# NuTube_Screamer_v1_1.net
KiCad netlist of a schematic drawn in EAGLE
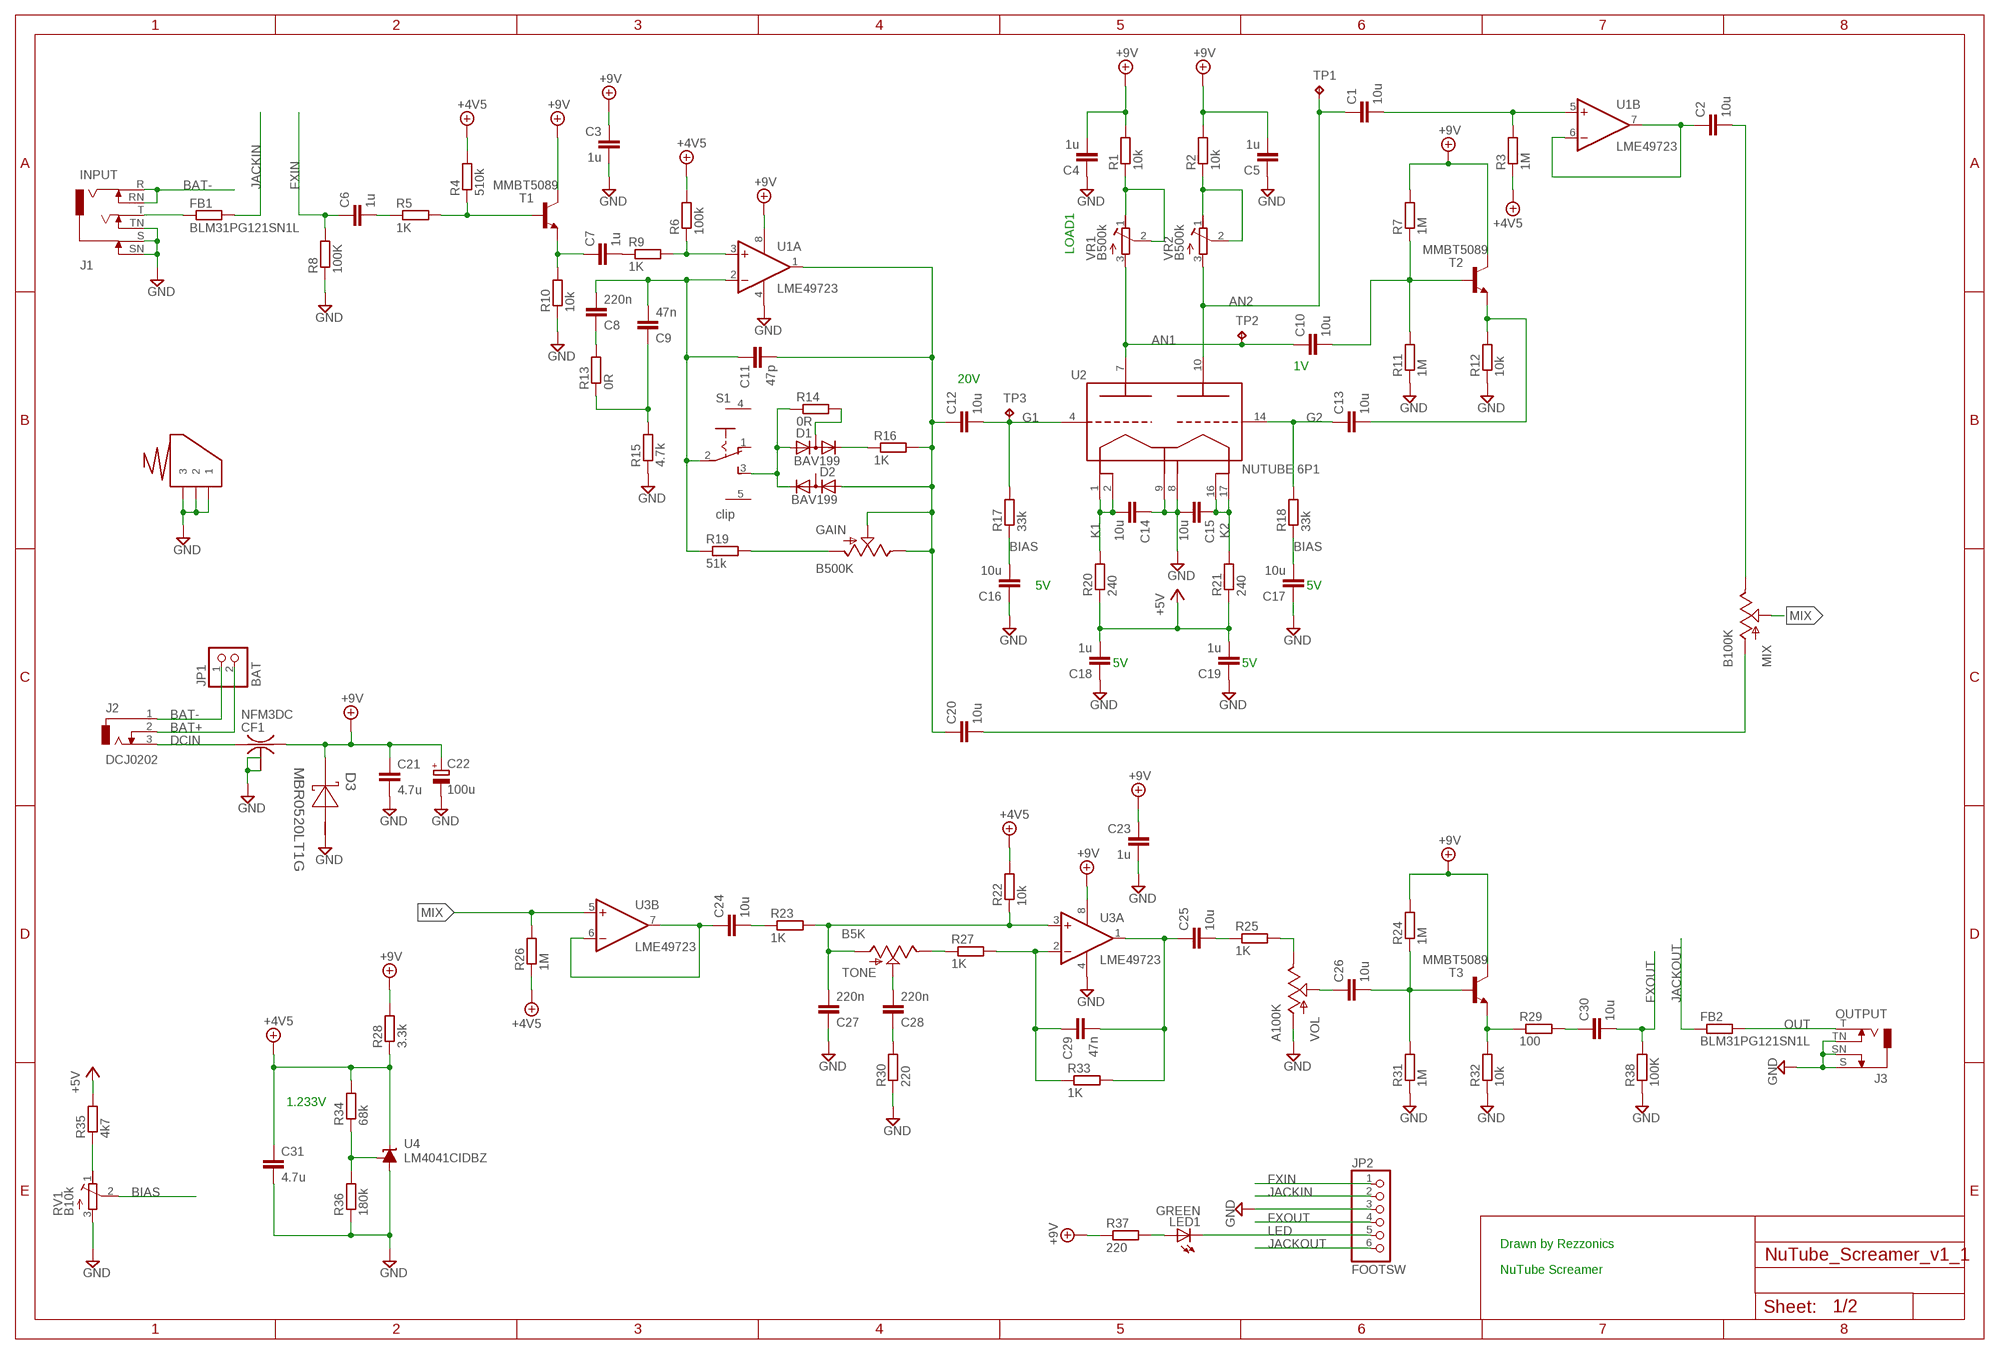
[diagram p0: schematic, sheet 1]
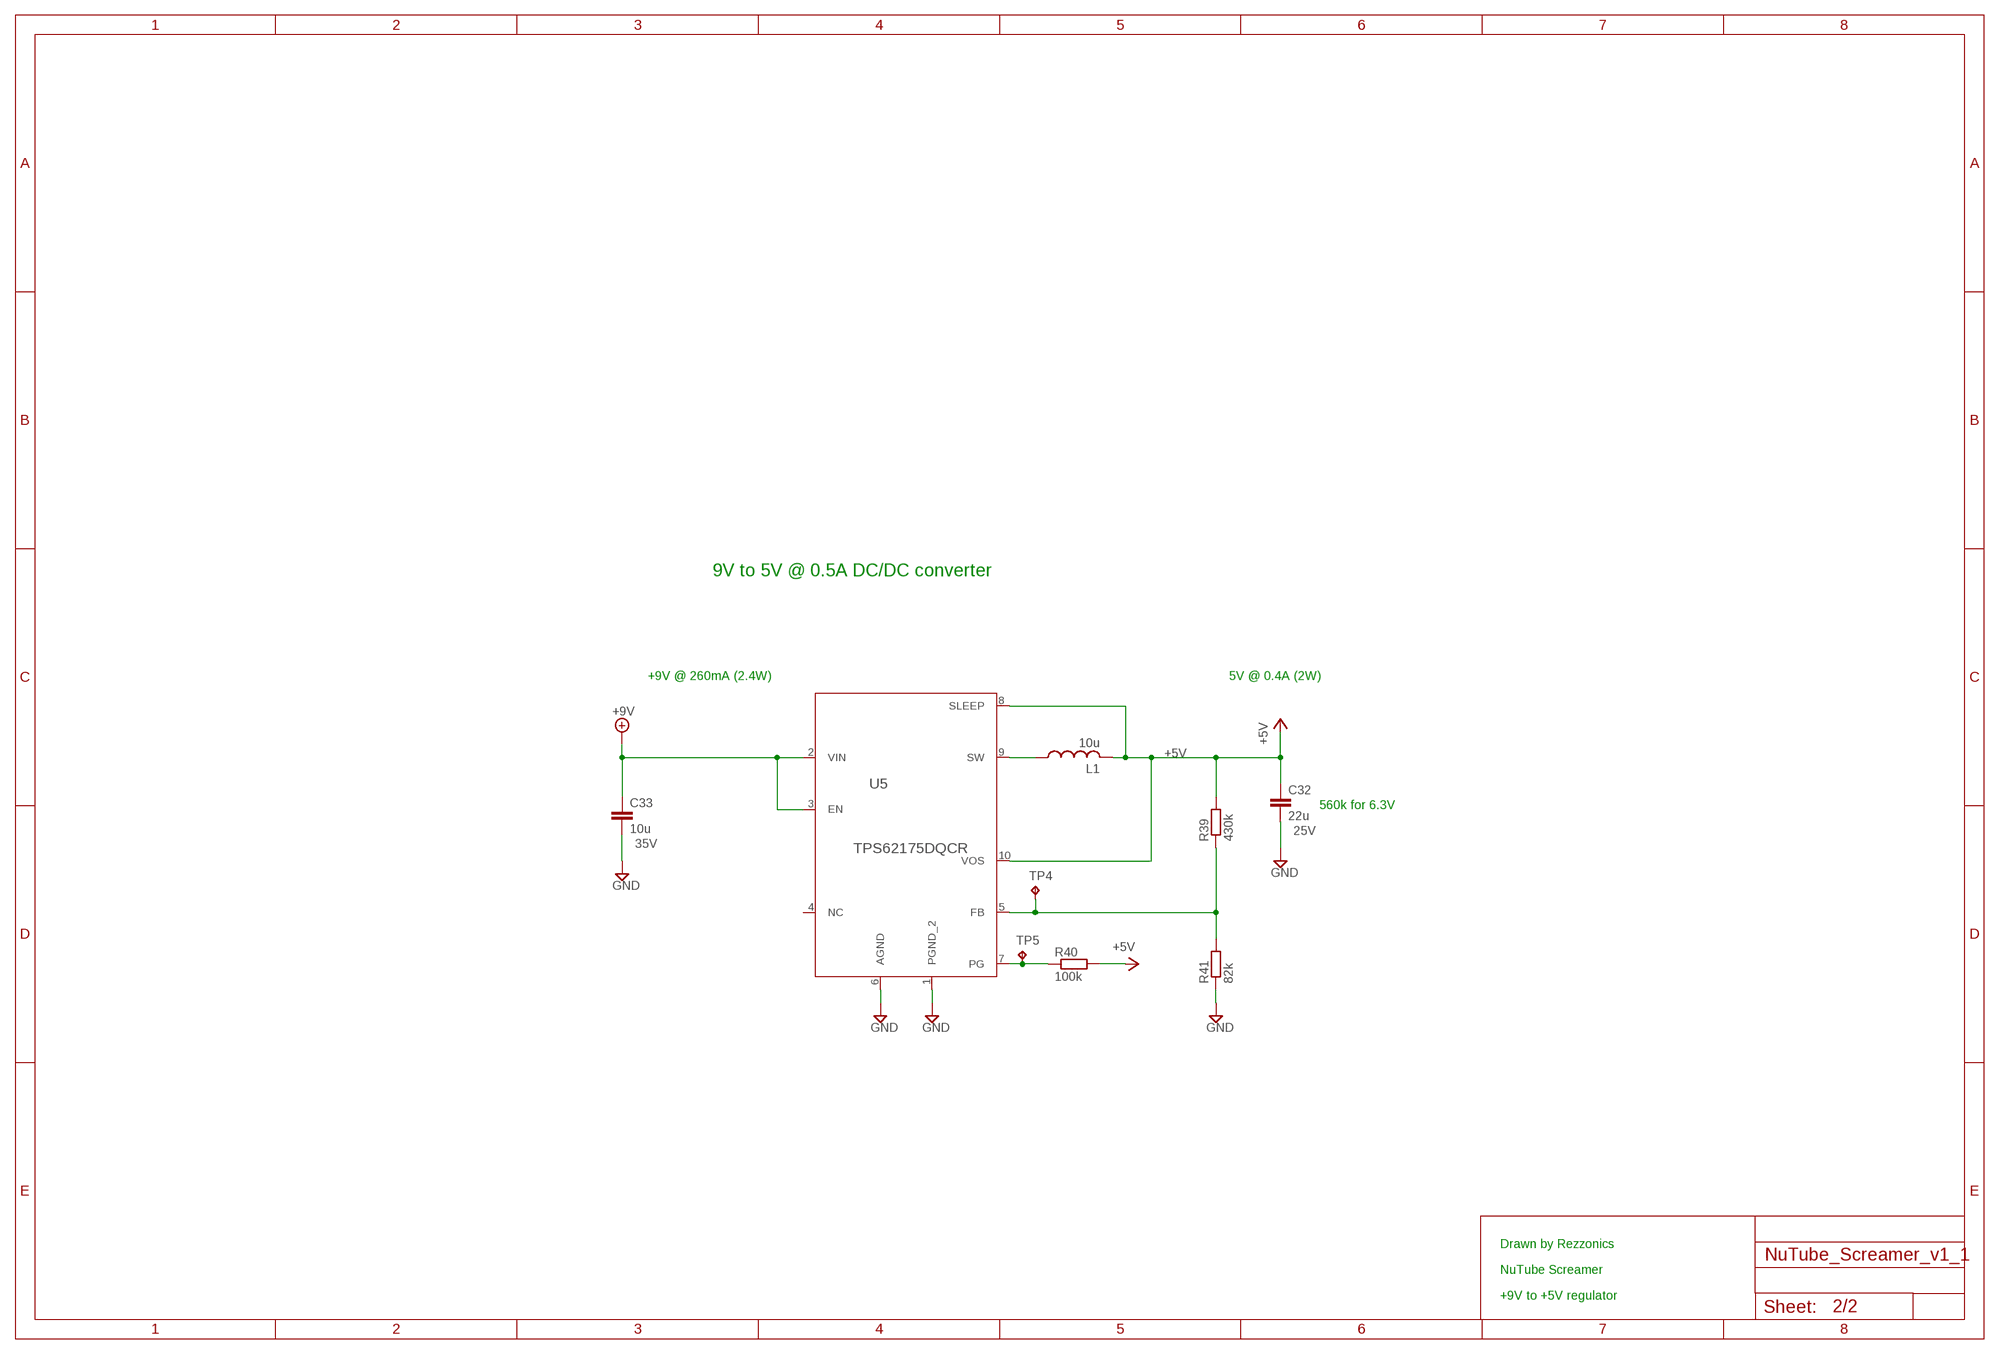
[diagram p1: schematic, sheet 2]

(export (version "E")
  (design (tool "Eeschema 10.0.6"))
  (components
    (comp (ref "C1")
      (value "10u")
      (footprint "eagle-import:C0805K")
      (fields (field (name "MPN") "GRM21BR6YA106KE43L"))
      (libsource (lib "eagle-import") (part "C-EUC0805K"))
    )
    (comp (ref "C2")
      (value "10u")
      (footprint "eagle-import:C0805K")
      (fields (field (name "MPN") "GRM21BR6YA106KE43L"))
      (libsource (lib "eagle-import") (part "C-EUC0805K"))
    )
    (comp (ref "C3")
      (value "1u")
      (footprint "eagle-import:C0603K")
      (fields (field (name "MPN") "GRM188R71H104KA93D") (field (name "PARTNO") "C1608X7R1V105K080AE"))
      (libsource (lib "eagle-import") (part "C-EUC0603K"))
    )
    (comp (ref "C4")
      (value "1u")
      (footprint "eagle-import:C0603K")
      (fields (field (name "MPN") "C1608X5R1H105K080AB") (field (name "PARTNO") "C1608X7R1V105K080AE"))
      (libsource (lib "eagle-import") (part "C-EUC0603K"))
    )
    (comp (ref "C5")
      (value "1u")
      (footprint "eagle-import:C0603K")
      (fields (field (name "MPN") "C1608X5R1H105K080AB") (field (name "PARTNO") "C1608X7R1V105K080AE"))
      (libsource (lib "eagle-import") (part "C-EUC0603K"))
    )
    (comp (ref "C6")
      (value "1u")
      (footprint "eagle-import:C0603K")
      (fields (field (name "MPN") "GRM188R71H104KA93D") (field (name "PARTNO") "C1608X7R1V105K080AE"))
      (libsource (lib "eagle-import") (part "C-EUC0603K"))
    )
    (comp (ref "C7")
      (value "1u")
      (footprint "eagle-import:C0603K")
      (fields (field (name "MPN") "GRM188R71H104KA93D") (field (name "PARTNO") "C1608X7R1V105K080AE"))
      (libsource (lib "eagle-import") (part "C-EUC0603K"))
    )
    (comp (ref "C8")
      (value "220n")
      (footprint "eagle-import:C0603K")
      (fields (field (name "MPN") "GRM188R71H104KA93D") (field (name "PARTNO") "GRM188R61H224KAC4D"))
      (libsource (lib "eagle-import") (part "C-EUC0603K"))
    )
    (comp (ref "C9")
      (value "47n")
      (footprint "eagle-import:C0603K")
      (fields (field (name "MPN") "GRM188R71H104KA93D") (field (name "PARTNO") "06035D473MAT2A"))
      (libsource (lib "eagle-import") (part "C-EUC0603K"))
    )
    (comp (ref "C10")
      (value "10u")
      (footprint "eagle-import:C0805K")
      (fields (field (name "MPN") "GRM21BR6YA106KE43L"))
      (libsource (lib "eagle-import") (part "C-EUC0805K"))
    )
    (comp (ref "C11")
      (value "47p")
      (footprint "eagle-import:C0603K")
      (fields (field (name "MPN") "GRM188R71H104KA93D") (field (name "PARTNO") "GCM1885C2A470JA16D"))
      (libsource (lib "eagle-import") (part "C-EUC0603K"))
    )
    (comp (ref "C12")
      (value "10u")
      (footprint "eagle-import:C0805K")
      (fields (field (name "MPN") "GRM21BR6YA106KE43L"))
      (libsource (lib "eagle-import") (part "C-EUC0805K"))
    )
    (comp (ref "C13")
      (value "10u")
      (footprint "eagle-import:C0805K")
      (fields (field (name "PARTNO") "GRM21BR6YA106KE43L"))
      (libsource (lib "eagle-import") (part "C-EUC0805K"))
    )
    (comp (ref "C14")
      (value "10u")
      (footprint "eagle-import:C0805K")
      (fields (field (name "MPN") "GRM21BR6YA106KE43L"))
      (libsource (lib "eagle-import") (part "C-EUC0805K"))
    )
    (comp (ref "C15")
      (value "10u")
      (footprint "eagle-import:C0805K")
      (fields (field (name "MPN") "GRM21BR6YA106KE43L"))
      (libsource (lib "eagle-import") (part "C-EUC0805K"))
    )
    (comp (ref "C16")
      (value "10u")
      (footprint "eagle-import:C0805K")
      (fields (field (name "MPN") "GRM21BR6YA106KE43L"))
      (libsource (lib "eagle-import") (part "C-EUC0805K"))
    )
    (comp (ref "C17")
      (value "10u")
      (footprint "eagle-import:C0805K")
      (fields (field (name "MPN") "GRM21BR6YA106KE43L"))
      (libsource (lib "eagle-import") (part "C-EUC0805K"))
    )
    (comp (ref "C18")
      (value "1u")
      (footprint "eagle-import:C0603K")
      (fields (field (name "MPN") "C1608X5R1H105K080AB") (field (name "PARTNO") "C1608X7R1V105K080AE"))
      (libsource (lib "eagle-import") (part "C-EUC0603K"))
    )
    (comp (ref "C19")
      (value "1u")
      (footprint "eagle-import:C0603K")
      (fields (field (name "MPN") "C1608X5R1H105K080AB") (field (name "PARTNO") "C1608X7R1V105K080AE"))
      (libsource (lib "eagle-import") (part "C-EUC0603K"))
    )
    (comp (ref "C20")
      (value "10u")
      (footprint "eagle-import:C0805K")
      (fields (field (name "MPN") "GRM21BR6YA106KE43L"))
      (libsource (lib "eagle-import") (part "C-EUC0805K"))
    )
    (comp (ref "C21")
      (value "4.7u")
      (footprint "eagle-import:C0805K")
      (fields (field (name "MPN") "GRM21BR61E475KA12L") (field (name "PARTNO") "C2012X5R1E475K125AB"))
      (libsource (lib "eagle-import") (part "C-EUC0805K"))
    )
    (comp (ref "C22")
      (value "100u")
      (footprint "eagle-import:PANASONIC_D")
      (fields (field (name "MPN") "EEE-1VA101XP"))
      (libsource (lib "eagle-import") (part "CPOL-EUD"))
    )
    (comp (ref "C23")
      (value "1u")
      (footprint "eagle-import:C0603K")
      (fields (field (name "MPN") "GRM188R71H104KA93D") (field (name "PARTNO") "C1608X7R1V105K080AE"))
      (libsource (lib "eagle-import") (part "C-EUC0603K"))
    )
    (comp (ref "C24")
      (value "10u")
      (footprint "eagle-import:C0805K")
      (fields (field (name "MPN") "GRM21BR6YA106KE43L"))
      (libsource (lib "eagle-import") (part "C-EUC0805K"))
    )
    (comp (ref "C25")
      (value "10u")
      (footprint "eagle-import:C0805K")
      (fields (field (name "MPN") "GRM21BR6YA106KE43L"))
      (libsource (lib "eagle-import") (part "C-EUC0805K"))
    )
    (comp (ref "C26")
      (value "10u")
      (footprint "eagle-import:C0805K")
      (fields (field (name "MPN") "GRM21BR6YA106KE43L"))
      (libsource (lib "eagle-import") (part "C-EUC0805K"))
    )
    (comp (ref "C27")
      (value "220n")
      (footprint "eagle-import:C0603K")
      (fields (field (name "MPN") "GRM188R71H104KA93D") (field (name "PARTNO") "GRM188R61H224KAC4D"))
      (libsource (lib "eagle-import") (part "C-EUC0603K"))
    )
    (comp (ref "C28")
      (value "220n")
      (footprint "eagle-import:C0603K")
      (fields (field (name "MPN") "GRM188R71H104KA93D") (field (name "PARTNO") "GRM188R61H224KAC4D"))
      (libsource (lib "eagle-import") (part "C-EUC0603K"))
    )
    (comp (ref "C29")
      (value "47n")
      (footprint "eagle-import:C0603K")
      (fields (field (name "MPN") "GRM188R71H104KA93D") (field (name "PARTNO") "06035D473MAT2A"))
      (libsource (lib "eagle-import") (part "C-EUC0603K"))
    )
    (comp (ref "C30")
      (value "10u")
      (footprint "eagle-import:C0805K")
      (fields (field (name "MPN") "GRM21BR6YA106KE43L"))
      (libsource (lib "eagle-import") (part "C-EUC0805K"))
    )
    (comp (ref "C31")
      (value "4.7u")
      (footprint "eagle-import:C0805K")
      (fields (field (name "MPN") "GRM21BR61E475KA12L") (field (name "PARTNO") "C2012X5R1E475K125AB"))
      (libsource (lib "eagle-import") (part "C-EUC0805K"))
    )
    (comp (ref "CF1")
      (value "NFM3DC")
      (footprint "eagle-import:NFM3DC")
      (fields
        (field (name "MF") "FARNELL")
        (field (name "MPN") "NFM3DCC470U1H3L")
        (field (name "MPN_1") "NFM3DPC223R1H3L")
        (field (name "PARTNO") "NFM3DPC223R1H3L")
      )
      (libsource (lib "eagle-import") (part "NFM3DC"))
    )
    (comp (ref "D1")
      (value "BAV199")
      (footprint "eagle-import:SOT23")
      (fields (field (name "PARTNO") "BAV199235"))
      (libsource (lib "eagle-import") (part "BAV199"))
    )
    (comp (ref "D2")
      (value "BAV199")
      (footprint "eagle-import:SOT23")
      (fields (field (name "PARTNO") "BAV199235"))
      (libsource (lib "eagle-import") (part "BAV199"))
    )
    (comp (ref "D3")
      (value "MBR0520LT1G")
      (footprint "eagle-import:SOD-123")
      (fields (field (name "MANUFACTURER_PART_NUMBER") "MBR0540T1G"))
      (libsource (lib "eagle-import") (part "MBR0540T1G"))
    )
    (comp (ref "FB1")
      (value "BLM31PG121SN1L")
      (footprint "eagle-import:R1206")
      (libsource (lib "eagle-import") (part "R-EU_R1206"))
    )
    (comp (ref "FB2")
      (value "BLM31PG121SN1L")
      (footprint "eagle-import:R1206")
      (libsource (lib "eagle-import") (part "R-EU_R1206"))
    )
    (comp (ref "GAIN")
      (value "B500K")
      (footprint "eagle-import:ALPS_POT")
      (fields (field (name "PARTNO") "PTV09A-4020S-B504"))
      (libsource (lib "eagle-import") (part "POT"))
    )
    (comp (ref "J1")
      (value "INPUT")
      (footprint "eagle-import:NEUTRIK-NMJ6HCD2")
      (fields (field (name "MPN") "NMJ6HCD2"))
      (libsource (lib "eagle-import") (part "STEREOSW3C"))
    )
    (comp (ref "J2")
      (value "DCJ0202")
      (footprint "eagle-import:DCJ0202")
      (fields (field (name "MPN") "163-179PH-EX") (field (name "PARTNO") "PJ-202A"))
      (libsource (lib "eagle-import") (part "DCJ0202"))
    )
    (comp (ref "J3")
      (value "OUTPUT")
      (footprint "eagle-import:NEUTRIK-NMJ4HCD2")
      (fields (field (name "MPN") "NMJ4HCD2"))
      (libsource (lib "eagle-import") (part "MONOSW3C"))
    )
    (comp (ref "JP1")
      (value "BAT")
      (footprint "eagle-import:1X02")
      (libsource (lib "eagle-import") (part "PINHD-1X2"))
    )
    (comp (ref "JP2")
      (value "FOOTSW")
      (footprint "eagle-import:1X06")
      (libsource (lib "eagle-import") (part "PINHD-1X6"))
    )
    (comp (ref "LED1")
      (value "GREEN")
      (footprint "eagle-import:LED5MM")
      (fields (field (name "MPN") "SSL-LX5093GD"))
      (libsource (lib "eagle-import") (part "LED5MM"))
    )
    (comp (ref "MIX")
      (value "B100K")
      (footprint "eagle-import:ALPS_POT")
      (fields (field (name "PARTNO") "PTV09A-4020S-B104"))
      (libsource (lib "eagle-import") (part "POT"))
    )
    (comp (ref "R1")
      (value "10k")
      (footprint "eagle-import:R0603")
      (fields (field (name "MPN") "ERJ-2RKF1002X") (field (name "PARTNO") "CR0603-FX-1002HLF"))
      (libsource (lib "eagle-import") (part "resistor_R-EU_R0603"))
    )
    (comp (ref "R2")
      (value "10k")
      (footprint "eagle-import:R0603")
      (fields (field (name "MPN") "ERJ-2RKF1002X") (field (name "PARTNO") "CR0603-FX-1002HLF"))
      (libsource (lib "eagle-import") (part "resistor_R-EU_R0603"))
    )
    (comp (ref "R3")
      (value "1M")
      (footprint "eagle-import:R0603@1")
      (fields (field (name "MPN") "CR0603-FX-1004ELF"))
      (libsource (lib "eagle-import") (part "R-EU_R0603"))
    )
    (comp (ref "R4")
      (value "510k")
      (footprint "eagle-import:R0603@1")
      (fields (field (name "MPN") "CR0603-FX-1004ELF") (field (name "PARTNO") "CR0603-FX-5103ELF"))
      (libsource (lib "eagle-import") (part "R-EU_R0603"))
    )
    (comp (ref "R5")
      (value "1K")
      (footprint "eagle-import:R0603@1")
      (fields (field (name "MPN") "CR0603-FX-1002HLF") (field (name "PARTNO") "ERJ-3EKF1001V"))
      (libsource (lib "eagle-import") (part "R-EU_R0603"))
    )
    (comp (ref "R6")
      (value "100k")
      (footprint "eagle-import:R0603@1")
      (fields (field (name "MPN") "CR0603-FX-1004ELF") (field (name "PARTNO") "ERJ-3EKF1003V"))
      (libsource (lib "eagle-import") (part "R-EU_R0603"))
    )
    (comp (ref "R7")
      (value "1M")
      (footprint "eagle-import:R0603@1")
      (fields (field (name "MPN") "CR0603-FX-1004ELF"))
      (libsource (lib "eagle-import") (part "R-EU_R0603"))
    )
    (comp (ref "R8")
      (value "100K")
      (footprint "eagle-import:R0603@1")
      (fields (field (name "MPN") "CR0603-FX-1004ELF"))
      (libsource (lib "eagle-import") (part "R-EU_R0603"))
    )
    (comp (ref "R9")
      (value "1K")
      (footprint "eagle-import:R0603@1")
      (fields (field (name "MPN") "CR0603-FX-1002HLF") (field (name "PARTNO") "ERJ-3EKF1001V"))
      (libsource (lib "eagle-import") (part "R-EU_R0603"))
    )
    (comp (ref "R10")
      (value "10k")
      (footprint "eagle-import:R0603@1")
      (fields (field (name "MPN") "CR0603-FX-1004ELF") (field (name "PARTNO") "CR0603-FX-1002HLF"))
      (libsource (lib "eagle-import") (part "R-EU_R0603"))
    )
    (comp (ref "R11")
      (value "1M")
      (footprint "eagle-import:R0603@1")
      (fields (field (name "MPN") "CR0603-FX-1004ELF"))
      (libsource (lib "eagle-import") (part "R-EU_R0603"))
    )
    (comp (ref "R12")
      (value "10k")
      (footprint "eagle-import:R0603@1")
      (fields (field (name "MPN") "CR0603-FX-1004ELF") (field (name "PARTNO") "CR0603-FX-1002HLF"))
      (libsource (lib "eagle-import") (part "R-EU_R0603"))
    )
    (comp (ref "R13")
      (value "0R")
      (footprint "eagle-import:R0603@1")
      (fields (field (name "MPN") "CR0603-FX-1002HLF") (field (name "PARTNO") "CRCW06030000ZSTB"))
      (libsource (lib "eagle-import") (part "R-EU_R0603"))
    )
    (comp (ref "R14")
      (value "0R")
      (footprint "eagle-import:R0603@1")
      (fields (field (name "MPN") "CR0603-FX-1002HLF") (field (name "PARTNO") "CRCW06030000ZSTB"))
      (libsource (lib "eagle-import") (part "R-EU_R0603"))
    )
    (comp (ref "R15")
      (value "4.7k")
      (footprint "eagle-import:R0603@1")
      (fields (field (name "MPN") "CR0603-FX-1004ELF") (field (name "PARTNO") "ERJ-3EKF4701V"))
      (libsource (lib "eagle-import") (part "R-EU_R0603"))
    )
    (comp (ref "R16")
      (value "1K")
      (footprint "eagle-import:R0603@1")
      (fields (field (name "MPN") "CR0603-FX-1002HLF") (field (name "PARTNO") "ERJ-3EKF1001V"))
      (libsource (lib "eagle-import") (part "R-EU_R0603"))
    )
    (comp (ref "R17")
      (value "33k")
      (footprint "eagle-import:R0603")
      (fields (field (name "MPN") "ERJ-2RKF3302X") (field (name "PARTNO") "CR0603-FX-3302ELF"))
      (libsource (lib "eagle-import") (part "resistor_R-EU_R0603"))
    )
    (comp (ref "R18")
      (value "33k")
      (footprint "eagle-import:R0603")
      (fields (field (name "MPN") "ERJ-2RKF3302X") (field (name "PARTNO") "CR0603-FX-3302ELF"))
      (libsource (lib "eagle-import") (part "resistor_R-EU_R0603"))
    )
    (comp (ref "R19")
      (value "51k")
      (footprint "eagle-import:R0603@1")
      (fields (field (name "MPN") "CR0603-FX-1002HLF") (field (name "PARTNO") "ERJ-3EKF5102V"))
      (libsource (lib "eagle-import") (part "R-EU_R0603"))
    )
    (comp (ref "R20")
      (value "240")
      (footprint "eagle-import:R0603")
      (fields (field (name "MPN") "ERJ-3EKF2400V"))
      (libsource (lib "eagle-import") (part "resistor_R-EU_R0603"))
    )
    (comp (ref "R21")
      (value "240")
      (footprint "eagle-import:R0603")
      (fields (field (name "MPN") "ERJ-3EKF2400V"))
      (libsource (lib "eagle-import") (part "resistor_R-EU_R0603"))
    )
    (comp (ref "R22")
      (value "10k")
      (footprint "eagle-import:R0603@1")
      (fields (field (name "MPN") "CR0603-FX-1004ELF") (field (name "PARTNO") "CR0603-FX-1002HLF"))
      (libsource (lib "eagle-import") (part "R-EU_R0603"))
    )
    (comp (ref "R23")
      (value "1K")
      (footprint "eagle-import:R0603@1")
      (fields (field (name "MPN") "CR0603-FX-1002HLF") (field (name "PARTNO") "ERJ-3EKF1001V"))
      (libsource (lib "eagle-import") (part "R-EU_R0603"))
    )
    (comp (ref "R24")
      (value "1M")
      (footprint "eagle-import:R0603@1")
      (fields (field (name "MPN") "CR0603-FX-1004ELF"))
      (libsource (lib "eagle-import") (part "R-EU_R0603"))
    )
    (comp (ref "R25")
      (value "1K")
      (footprint "eagle-import:R0603@1")
      (fields (field (name "MPN") "CR0603-FX-1002HLF") (field (name "PARTNO") "ERJ-3EKF1001V"))
      (libsource (lib "eagle-import") (part "R-EU_R0603"))
    )
    (comp (ref "R26")
      (value "1M")
      (footprint "eagle-import:R0603@1")
      (fields (field (name "MPN") "CR0603-FX-1004ELF"))
      (libsource (lib "eagle-import") (part "R-EU_R0603"))
    )
    (comp (ref "R27")
      (value "1K")
      (footprint "eagle-import:R0603@1")
      (fields (field (name "MPN") "CR0603-FX-1002HLF") (field (name "PARTNO") "ERJ-3EKF1001V"))
      (libsource (lib "eagle-import") (part "R-EU_R0603"))
    )
    (comp (ref "R28")
      (value "3.3k")
      (footprint "eagle-import:R0603@1")
      (fields (field (name "MPN") "RC0603FR-073K3L"))
      (libsource (lib "eagle-import") (part "R-EU_R0603"))
    )
    (comp (ref "R29")
      (value "100")
      (footprint "eagle-import:R0603@1")
      (fields (field (name "MPN") "CR0603-FX-1002HLF") (field (name "PARTNO") "RC0603FR-07100RL"))
      (libsource (lib "eagle-import") (part "R-EU_R0603"))
    )
    (comp (ref "R30")
      (value "220")
      (footprint "eagle-import:R0603@1")
      (fields (field (name "MPN") "CR0603-FX-1004ELF") (field (name "PARTNO") "ERJ-PA3F2200V"))
      (libsource (lib "eagle-import") (part "R-EU_R0603"))
    )
    (comp (ref "R31")
      (value "1M")
      (footprint "eagle-import:R0603@1")
      (fields (field (name "MPN") "CR0603-FX-1004ELF"))
      (libsource (lib "eagle-import") (part "R-EU_R0603"))
    )
    (comp (ref "R32")
      (value "10k")
      (footprint "eagle-import:R0603@1")
      (fields (field (name "MPN") "CR0603-FX-1004ELF") (field (name "PARTNO") "CR0603-FX-1002HLF"))
      (libsource (lib "eagle-import") (part "R-EU_R0603"))
    )
    (comp (ref "R33")
      (value "1K")
      (footprint "eagle-import:R0603@1")
      (fields (field (name "MPN") "CR0603-FX-1002HLF") (field (name "PARTNO") "ERJ-3EKF1001V"))
      (libsource (lib "eagle-import") (part "R-EU_R0603"))
    )
    (comp (ref "R34")
      (value "68k")
      (footprint "eagle-import:R0603@1")
      (fields (field (name "MPN") "RC0603FR-0768KL"))
      (libsource (lib "eagle-import") (part "R-EU_R0603"))
    )
    (comp (ref "R35")
      (value "4k7")
      (footprint "eagle-import:R0603")
      (fields (field (name "MPN") "ERJ-2RKF4701X") (field (name "PARTNO") "ERJ-3EKF4701V"))
      (libsource (lib "eagle-import") (part "resistor_R-EU_R0603"))
    )
    (comp (ref "R36")
      (value "180k")
      (footprint "eagle-import:R0603@1")
      (fields (field (name "MPN") "RC0603FR-07180KL"))
      (libsource (lib "eagle-import") (part "R-EU_R0603"))
    )
    (comp (ref "R37")
      (value "220")
      (footprint "eagle-import:R0603@1")
      (fields (field (name "MPN") "ERJ-PA3F2200V"))
      (libsource (lib "eagle-import") (part "R-EU_R0603"))
    )
    (comp (ref "R38")
      (value "100K")
      (footprint "eagle-import:R0603@1")
      (fields (field (name "MPN") "CR0603-FX-1004ELF"))
      (libsource (lib "eagle-import") (part "R-EU_R0603"))
    )
    (comp (ref "RV1")
      (value "B10k")
      (footprint "eagle-import:RTRIM3314G")
      (fields (field (name "MPN") "3314G-2-103E"))
      (libsource (lib "eagle-import") (part "R-TRIMM3314G"))
    )
    (comp (ref "S1")
      (value "clip")
      (footprint "eagle-import:MHS122K")
      (fields (field (name "PARTNO") "MHS122K"))
      (libsource (lib "eagle-import") (part "SPDT"))
    )
    (comp (ref "T1")
      (value "MMBT5089")
      (footprint "eagle-import:SOT23-BEC")
      (libsource (lib "eagle-import") (part "-NPN-SOT23-BECMMBT2222ALT1"))
    )
    (comp (ref "T2")
      (value "MMBT5089")
      (footprint "eagle-import:SOT23-BEC")
      (libsource (lib "eagle-import") (part "-NPN-SOT23-BECMMBT2222ALT1"))
    )
    (comp (ref "T3")
      (value "MMBT5089")
      (footprint "eagle-import:SOT23-BEC")
      (libsource (lib "eagle-import") (part "-NPN-SOT23-BECMMBT2222ALT1"))
    )
    (comp (ref "TONE")
      (value "B5K")
      (footprint "eagle-import:ALPS_POT")
      (fields (field (name "PARTNO") "PTV09A-4020F-B502"))
      (libsource (lib "eagle-import") (part "POT"))
    )
    (comp (ref "TP1")
      (value "TPTP10R")
      (footprint "eagle-import:TP10R")
      (fields (field (name "PARTNO") "1249"))
      (libsource (lib "eagle-import") (part "TPTP10R"))
    )
    (comp (ref "TP2")
      (value "TPTP10R")
      (footprint "eagle-import:TP10R")
      (fields (field (name "PARTNO") "1249"))
      (libsource (lib "eagle-import") (part "TPTP10R"))
    )
    (comp (ref "TP3")
      (value "TPTP10R")
      (footprint "eagle-import:TP10R")
      (fields (field (name "PARTNO") "1249"))
      (libsource (lib "eagle-import") (part "TPTP10R"))
    )
    (comp (ref "U1")
      (value "LME49723")
      (footprint "eagle-import:SO08")
      (fields (field (name "MPN") "LME49723MA/NOPB") (field (name "PARTNO") "LME49723MA/NOPB"))
      (libsource (lib "eagle-import") (part "RC4559D"))
    )
    (comp (ref "U2")
      (value "NUTUBE 6P1")
      (footprint "eagle-import:NUTUBE_6P1_1")
      (fields (field (name "PARTNO") "831-87-032-10-001101"))
      (libsource (lib "eagle-import") (part "NUTUBE_6P1_1"))
    )
    (comp (ref "U3")
      (value "LME49723")
      (footprint "eagle-import:SO08")
      (fields (field (name "MPN") "LME49723MA/NOPB") (field (name "PARTNO") "LME49723MA/NOPB"))
      (libsource (lib "eagle-import") (part "RC4559D"))
    )
    (comp (ref "U4")
      (value "LM4041CIDBZ")
      (footprint "eagle-import:DBZ_R-PDSO-G3")
      (fields
        (field (name "MF") "TEXAS INSTRUMENT CONNECTORS")
        (field (name "MPN") "LM4041CIDBZR")
        (field (name "MPN_1") "LM4041CIDBZR")
      )
      (libsource (lib "eagle-import") (part "LM4041IDBZC"))
    )
    (comp (ref "VOL")
      (value "A100K")
      (footprint "eagle-import:ALPS_POT")
      (fields (field (name "PARTNO") "PTV09A-4020S-A104"))
      (libsource (lib "eagle-import") (part "POT"))
    )
    (comp (ref "VR1")
      (value "B500k")
      (footprint "eagle-import:RTRIM3314G")
      (fields (field (name "MPN") "3314G-1-504E"))
      (libsource (lib "eagle-import") (part "R-TRIMM3314G"))
    )
    (comp (ref "VR2")
      (value "B500k")
      (footprint "eagle-import:RTRIM3314G")
      (fields (field (name "MPN") "3314G-1-504E"))
      (libsource (lib "eagle-import") (part "R-TRIMM3314G"))
    )
    (comp (ref "X1")
      (value "CLIPAAA-CLIPAAA_2")
      (footprint "eagle-import:CLIPAAA_2")
      (fields (field (name "MPN") "591"))
      (libsource (lib "eagle-import") (part "CLIPAAA-CLIPAAA_2"))
    )
    (comp (ref "C32")
      (value "22u")
      (footprint "eagle-import:C0805K")
      (fields (field (name "MPN") "C2012X5R1V226M125AC") (field (name "VOLT") "25V"))
      (libsource (lib "eagle-import") (part "C-EUC0805K"))
    )
    (comp (ref "C33")
      (value "10u")
      (footprint "eagle-import:C0805K")
      (fields (field (name "MPN") "GRM21BR6YA106KE43L") (field (name "VOLT") "35V"))
      (libsource (lib "eagle-import") (part "C-EUC0805K"))
    )
    (comp (ref "L1")
      (value "10u")
      (footprint "eagle-import:SRN4018")
      (fields (field (name "MPN") "SRN4018-100M"))
      (libsource (lib "eagle-import") (part "SRN4018"))
    )
    (comp (ref "R39")
      (value "430k")
      (footprint "eagle-import:R0603")
      (fields (field (name "MPN") "ERJ-2GEJ434X") (field (name "PARTNO") "CR0603-FX-4303ELF"))
      (libsource (lib "eagle-import") (part "resistor_R-EU_R0603"))
    )
    (comp (ref "R40")
      (value "100k")
      (footprint "eagle-import:R0603")
      (fields (field (name "MPN") "ERJ-2RKF1003X") (field (name "PARTNO") "ERJ-3EKF1003V"))
      (libsource (lib "eagle-import") (part "resistor_R-EU_R0603"))
    )
    (comp (ref "R41")
      (value "82k")
      (footprint "eagle-import:R0603")
      (fields (field (name "MPN") "ERJ-2RKF8202X") (field (name "PARTNO") "ERJ-3EKF8202V"))
      (libsource (lib "eagle-import") (part "resistor_R-EU_R0603"))
    )
    (comp (ref "TP4")
      (value "TPTP10R")
      (footprint "eagle-import:TP10R")
      (fields (field (name "PARTNO") "1249"))
      (libsource (lib "eagle-import") (part "TPTP10R"))
    )
    (comp (ref "TP5")
      (value "TPTP10R")
      (footprint "eagle-import:TP10R")
      (fields (field (name "PARTNO") "1249"))
      (libsource (lib "eagle-import") (part "TPTP10R"))
    )
    (comp (ref "U5")
      (value "TPS62175DQCR")
      (footprint "eagle-import:R-PWSON-N10")
      (libsource (lib "eagle-import") (part "TPS62175DQCR"))
    )
  )
  (nets
    (net (code "1") (name "+4.5V") (class "Default")
      (node (ref "C31") (pin "1") (pinfunction "1_1") (pintype "passive"))
      (node (ref "R22") (pin "2") (pinfunction "2_2") (pintype "passive"))
      (node (ref "R26") (pin "1") (pinfunction "1_1") (pintype "passive"))
      (node (ref "R28") (pin "1") (pinfunction "1_1") (pintype "passive"))
      (node (ref "R3") (pin "1") (pinfunction "1_1") (pintype "passive"))
      (node (ref "R34") (pin "2") (pinfunction "2_2") (pintype "passive"))
      (node (ref "R4") (pin "2") (pinfunction "2_2") (pintype "passive"))
      (node (ref "R6") (pin "2") (pinfunction "2_2") (pintype "passive"))
      (node (ref "U4") (pin "2") (pinfunction "C_2") (pintype "passive"))
    )
    (net (code "2") (name "+5V") (class "Default")
      (node (ref "C18") (pin "2") (pinfunction "2_2") (pintype "passive"))
      (node (ref "C19") (pin "2") (pinfunction "2_2") (pintype "passive"))
      (node (ref "C32") (pin "1") (pinfunction "1_1") (pintype "passive"))
      (node (ref "L1") (pin "2") (pinfunction "2_2") (pintype "passive"))
      (node (ref "R20") (pin "1") (pinfunction "1_1") (pintype "passive"))
      (node (ref "R21") (pin "1") (pinfunction "1_1") (pintype "passive"))
      (node (ref "R35") (pin "2") (pinfunction "2_2") (pintype "passive"))
      (node (ref "R39") (pin "2") (pinfunction "2_2") (pintype "passive"))
      (node (ref "R40") (pin "2") (pinfunction "2_2") (pintype "passive"))
      (node (ref "U5") (pin "10") (pinfunction "VOS_10") (pintype "passive"))
      (node (ref "U5") (pin "8") (pinfunction "SLEEP_8") (pintype "passive"))
    )
    (net (code "3") (name "+9V") (class "Default")
      (node (ref "C21") (pin "1") (pinfunction "1_1") (pintype "passive"))
      (node (ref "C22") (pin "+") (pinfunction "+_+") (pintype "passive"))
      (node (ref "C23") (pin "1") (pinfunction "1_1") (pintype "passive"))
      (node (ref "C3") (pin "1") (pinfunction "1_1") (pintype "passive"))
      (node (ref "C33") (pin "1") (pinfunction "1_1") (pintype "passive"))
      (node (ref "C4") (pin "2") (pinfunction "2_2") (pintype "passive"))
      (node (ref "C5") (pin "2") (pinfunction "2_2") (pintype "passive"))
      (node (ref "CF1") (pin "3") (pinfunction "3_3") (pintype "passive"))
      (node (ref "D3") (pin "1") (pinfunction "K_1") (pintype "passive"))
      (node (ref "R1") (pin "2") (pinfunction "2_2") (pintype "passive"))
      (node (ref "R2") (pin "2") (pinfunction "2_2") (pintype "passive"))
      (node (ref "R24") (pin "2") (pinfunction "2_2") (pintype "passive"))
      (node (ref "R28") (pin "2") (pinfunction "2_2") (pintype "passive"))
      (node (ref "R37") (pin "1") (pinfunction "1_1") (pintype "passive"))
      (node (ref "R7") (pin "2") (pinfunction "2_2") (pintype "passive"))
      (node (ref "T1") (pin "C") (pinfunction "C_C") (pintype "passive"))
      (node (ref "T2") (pin "C") (pinfunction "C_C") (pintype "passive"))
      (node (ref "T3") (pin "C") (pinfunction "C_C") (pintype "passive"))
      (node (ref "U1") (pin "8") (pinfunction "V+_8") (pintype "power_in"))
      (node (ref "U3") (pin "8") (pinfunction "V+_8") (pintype "power_in"))
      (node (ref "U5") (pin "2") (pinfunction "VIN_2") (pintype "passive"))
      (node (ref "U5") (pin "3") (pinfunction "EN_3") (pintype "passive"))
    )
    (net (code "4") (name "AN1") (class "Default")
      (node (ref "C10") (pin "1") (pinfunction "1_1") (pintype "passive"))
      (node (ref "TP2") (pin "TP") (pinfunction "TP_TP") (pintype "input"))
      (node (ref "U2") (pin "7") (pinfunction "A1_7_7") (pintype "passive"))
      (node (ref "VR1") (pin "3") (pinfunction "A_3") (pintype "passive"))
    )
    (net (code "5") (name "AN2") (class "Default")
      (node (ref "C1") (pin "1") (pinfunction "1_1") (pintype "passive"))
      (node (ref "TP1") (pin "TP") (pinfunction "TP_TP") (pintype "input"))
      (node (ref "U2") (pin "10") (pinfunction "A2_10_10") (pintype "passive"))
      (node (ref "VR2") (pin "3") (pinfunction "A_3") (pintype "passive"))
    )
    (net (code "6") (name "BAT+") (class "Default")
      (node (ref "J2") (pin "2") (pinfunction "2_2") (pintype "passive"))
      (node (ref "JP1") (pin "2") (pinfunction "2_2") (pintype "passive"))
    )
    (net (code "7") (name "BAT-") (class "Default")
      (node (ref "J1") (pin "R") (pinfunction "R_R") (pintype "passive"))
      (node (ref "J1") (pin "RN") (pinfunction "RN_RN") (pintype "passive"))
      (node (ref "J2") (pin "1") (pinfunction "1_1") (pintype "passive"))
      (node (ref "JP1") (pin "1") (pinfunction "1_1") (pintype "passive"))
    )
    (net (code "8") (name "BIAS") (class "Default")
      (node (ref "C16") (pin "2") (pinfunction "2_2") (pintype "passive"))
      (node (ref "C17") (pin "2") (pinfunction "2_2") (pintype "passive"))
      (node (ref "R17") (pin "1") (pinfunction "1_1") (pintype "passive"))
      (node (ref "R18") (pin "1") (pinfunction "1_1") (pintype "passive"))
      (node (ref "RV1") (pin "2") (pinfunction "S_2") (pintype "passive"))
    )
    (net (code "9") (name "DCIN") (class "Default")
      (node (ref "CF1") (pin "1") (pinfunction "1_1") (pintype "passive"))
      (node (ref "J2") (pin "3") (pinfunction "3_3") (pintype "passive"))
    )
    (net (code "10") (name "FXIN") (class "Default")
      (node (ref "C6") (pin "1") (pinfunction "1_1") (pintype "passive"))
      (node (ref "JP2") (pin "1") (pinfunction "1_1") (pintype "passive"))
      (node (ref "R8") (pin "2") (pinfunction "2_2") (pintype "passive"))
    )
    (net (code "11") (name "FXOUT") (class "Default")
      (node (ref "C30") (pin "2") (pinfunction "2_2") (pintype "passive"))
      (node (ref "JP2") (pin "4") (pinfunction "4_4") (pintype "passive"))
      (node (ref "R38") (pin "2") (pinfunction "2_2") (pintype "passive"))
    )
    (net (code "12") (name "G1") (class "Default")
      (node (ref "C12") (pin "2") (pinfunction "2_2") (pintype "passive"))
      (node (ref "R17") (pin "2") (pinfunction "2_2") (pintype "passive"))
      (node (ref "TP3") (pin "TP") (pinfunction "TP_TP") (pintype "input"))
      (node (ref "U2") (pin "4") (pinfunction "G1_4_4") (pintype "passive"))
    )
    (net (code "13") (name "G2") (class "Default")
      (node (ref "C13") (pin "1") (pinfunction "1_1") (pintype "passive"))
      (node (ref "R18") (pin "2") (pinfunction "2_2") (pintype "passive"))
      (node (ref "U2") (pin "14") (pinfunction "G2_14_14") (pintype "passive"))
    )
    (net (code "14") (name "GND") (class "Default")
      (node (ref "C14") (pin "1") (pinfunction "1_1") (pintype "passive"))
      (node (ref "C15") (pin "2") (pinfunction "2_2") (pintype "passive"))
      (node (ref "C16") (pin "1") (pinfunction "1_1") (pintype "passive"))
      (node (ref "C17") (pin "1") (pinfunction "1_1") (pintype "passive"))
      (node (ref "C18") (pin "1") (pinfunction "1_1") (pintype "passive"))
      (node (ref "C19") (pin "1") (pinfunction "1_1") (pintype "passive"))
      (node (ref "C21") (pin "2") (pinfunction "2_2") (pintype "passive"))
      (node (ref "C22") (pin "-") (pinfunction "-_-") (pintype "passive"))
      (node (ref "C23") (pin "2") (pinfunction "2_2") (pintype "passive"))
      (node (ref "C27") (pin "1") (pinfunction "1_1") (pintype "passive"))
      (node (ref "C3") (pin "2") (pinfunction "2_2") (pintype "passive"))
      (node (ref "C31") (pin "2") (pinfunction "2_2") (pintype "passive"))
      (node (ref "C32") (pin "2") (pinfunction "2_2") (pintype "passive"))
      (node (ref "C33") (pin "2") (pinfunction "2_2") (pintype "passive"))
      (node (ref "C4") (pin "1") (pinfunction "1_1") (pintype "passive"))
      (node (ref "C5") (pin "1") (pinfunction "1_1") (pintype "passive"))
      (node (ref "CF1") (pin "2@1") (pinfunction "2_2@1") (pintype "passive"))
      (node (ref "CF1") (pin "2@2") (pinfunction "2_2@2") (pintype "passive"))
      (node (ref "D3") (pin "2") (pinfunction "A_2") (pintype "passive"))
      (node (ref "J1") (pin "S") (pinfunction "S_S") (pintype "passive"))
      (node (ref "J1") (pin "SN") (pinfunction "SN_SN") (pintype "passive"))
      (node (ref "J1") (pin "TN") (pinfunction "TN_TN") (pintype "passive"))
      (node (ref "J3") (pin "S") (pinfunction "S_S") (pintype "passive"))
      (node (ref "J3") (pin "SN") (pinfunction "SN_SN") (pintype "passive"))
      (node (ref "J3") (pin "TN") (pinfunction "TN_TN") (pintype "passive"))
      (node (ref "JP2") (pin "3") (pinfunction "3_3") (pintype "passive"))
      (node (ref "R10") (pin "1") (pinfunction "1_1") (pintype "passive"))
      (node (ref "R11") (pin "1") (pinfunction "1_1") (pintype "passive"))
      (node (ref "R12") (pin "1") (pinfunction "1_1") (pintype "passive"))
      (node (ref "R15") (pin "1") (pinfunction "1_1") (pintype "passive"))
      (node (ref "R30") (pin "1") (pinfunction "1_1") (pintype "passive"))
      (node (ref "R31") (pin "1") (pinfunction "1_1") (pintype "passive"))
      (node (ref "R32") (pin "1") (pinfunction "1_1") (pintype "passive"))
      (node (ref "R36") (pin "1") (pinfunction "1_1") (pintype "passive"))
      (node (ref "R38") (pin "1") (pinfunction "1_1") (pintype "passive"))
      (node (ref "R41") (pin "1") (pinfunction "1_1") (pintype "passive"))
      (node (ref "R8") (pin "1") (pinfunction "1_1") (pintype "passive"))
      (node (ref "RV1") (pin "3") (pinfunction "A_3") (pintype "passive"))
      (node (ref "U1") (pin "4") (pinfunction "V-_4") (pintype "power_in"))
      (node (ref "U2") (pin "8") (pinfunction "GND_8_8") (pintype "power_in"))
      (node (ref "U2") (pin "9") (pinfunction "F2_9_9") (pintype "passive"))
      (node (ref "U3") (pin "4") (pinfunction "V-_4") (pintype "power_in"))
      (node (ref "U4") (pin "3") (pinfunction "A_3") (pintype "passive"))
      (node (ref "U5") (pin "1") (pinfunction "PGND_2_1") (pintype "passive"))
      (node (ref "U5") (pin "6") (pinfunction "AGND_6") (pintype "passive"))
      (node (ref "VOL") (pin "P$1") (pinfunction "A_P$1") (pintype "passive"))
      (node (ref "X1") (pin "1") (pinfunction "1_1") (pintype "passive"))
      (node (ref "X1") (pin "2") (pinfunction "2_2") (pintype "passive"))
      (node (ref "X1") (pin "3") (pinfunction "3_3") (pintype "passive"))
    )
    (net (code "15") (name "JACKIN") (class "Default")
      (node (ref "FB1") (pin "2") (pinfunction "2_2") (pintype "passive"))
      (node (ref "JP2") (pin "2") (pinfunction "2_2") (pintype "passive"))
    )
    (net (code "16") (name "JACKOUT") (class "Default")
      (node (ref "FB2") (pin "1") (pinfunction "1_1") (pintype "passive"))
      (node (ref "JP2") (pin "6") (pinfunction "6_6") (pintype "passive"))
    )
    (net (code "17") (name "K1") (class "Default")
      (node (ref "C14") (pin "2") (pinfunction "2_2") (pintype "passive"))
      (node (ref "R20") (pin "2") (pinfunction "2_2") (pintype "passive"))
      (node (ref "U2") (pin "1") (pinfunction "F1_1_1") (pintype "passive"))
      (node (ref "U2") (pin "2") (pinfunction "F1_2_2") (pintype "passive"))
    )
    (net (code "18") (name "K2") (class "Default")
      (node (ref "C15") (pin "1") (pinfunction "1_1") (pintype "passive"))
      (node (ref "R21") (pin "2") (pinfunction "2_2") (pintype "passive"))
      (node (ref "U2") (pin "16") (pinfunction "F3_16_16") (pintype "passive"))
      (node (ref "U2") (pin "17") (pinfunction "F3_17_17") (pintype "passive"))
    )
    (net (code "19") (name "LED") (class "Default")
      (node (ref "JP2") (pin "5") (pinfunction "5_5") (pintype "passive"))
      (node (ref "LED1") (pin "K") (pinfunction "C_K") (pintype "passive"))
    )
    (net (code "20") (name "MIX") (class "Default")
      (node (ref "MIX") (pin "P$2") (pinfunction "S_P$2") (pintype "passive"))
      (node (ref "R26") (pin "2") (pinfunction "2_2") (pintype "passive"))
      (node (ref "U3") (pin "5") (pinfunction "+IN_5") (pintype "input"))
    )
    (net (code "21") (name "Net-(C6-Pad2)") (class "Default")
      (node (ref "C6") (pin "2") (pinfunction "2_2") (pintype "passive"))
      (node (ref "R5") (pin "1") (pinfunction "1_1") (pintype "passive"))
    )
    (net (code "22") (name "Net-(C7-Pad1)") (class "Default")
      (node (ref "C7") (pin "1") (pinfunction "1_1") (pintype "passive"))
      (node (ref "R10") (pin "2") (pinfunction "2_2") (pintype "passive"))
      (node (ref "T1") (pin "E") (pinfunction "E_E") (pintype "passive"))
    )
    (net (code "23") (name "Net-(C7-Pad2)") (class "Default")
      (node (ref "C7") (pin "2") (pinfunction "2_2") (pintype "passive"))
      (node (ref "R9") (pin "1") (pinfunction "1_1") (pintype "passive"))
    )
    (net (code "24") (name "Net-(C8-Pad1)") (class "Default")
      (node (ref "C8") (pin "1") (pinfunction "1_1") (pintype "passive"))
      (node (ref "R13") (pin "2") (pinfunction "2_2") (pintype "passive"))
    )
    (net (code "25") (name "Net-(C9-Pad1)") (class "Default")
      (node (ref "C9") (pin "1") (pinfunction "1_1") (pintype "passive"))
      (node (ref "R13") (pin "1") (pinfunction "1_1") (pintype "passive"))
      (node (ref "R15") (pin "2") (pinfunction "2_2") (pintype "passive"))
    )
    (net (code "26") (name "Net-(C10-Pad2)") (class "Default")
      (node (ref "C10") (pin "2") (pinfunction "2_2") (pintype "passive"))
      (node (ref "R11") (pin "2") (pinfunction "2_2") (pintype "passive"))
      (node (ref "R7") (pin "1") (pinfunction "1_1") (pintype "passive"))
      (node (ref "T2") (pin "B") (pinfunction "B_B") (pintype "passive"))
    )
    (net (code "27") (name "Net-(C13-Pad2)") (class "Default")
      (node (ref "C13") (pin "2") (pinfunction "2_2") (pintype "passive"))
      (node (ref "R12") (pin "2") (pinfunction "2_2") (pintype "passive"))
      (node (ref "T2") (pin "E") (pinfunction "E_E") (pintype "passive"))
    )
    (net (code "28") (name "Net-(C24-Pad2)") (class "Default")
      (node (ref "C24") (pin "2") (pinfunction "2_2") (pintype "passive"))
      (node (ref "R23") (pin "1") (pinfunction "1_1") (pintype "passive"))
    )
    (net (code "29") (name "Net-(C25-Pad2)") (class "Default")
      (node (ref "C25") (pin "2") (pinfunction "2_2") (pintype "passive"))
      (node (ref "R25") (pin "1") (pinfunction "1_1") (pintype "passive"))
    )
    (net (code "30") (name "Net-(C26-Pad2)") (class "Default")
      (node (ref "C26") (pin "2") (pinfunction "2_2") (pintype "passive"))
      (node (ref "R24") (pin "1") (pinfunction "1_1") (pintype "passive"))
      (node (ref "R31") (pin "2") (pinfunction "2_2") (pintype "passive"))
      (node (ref "T3") (pin "B") (pinfunction "B_B") (pintype "passive"))
    )
    (net (code "31") (name "Net-(C28-Pad1)") (class "Default")
      (node (ref "C28") (pin "1") (pinfunction "1_1") (pintype "passive"))
      (node (ref "R30") (pin "2") (pinfunction "2_2") (pintype "passive"))
    )
    (net (code "32") (name "Net-(C30-Pad1)") (class "Default")
      (node (ref "C30") (pin "1") (pinfunction "1_1") (pintype "passive"))
      (node (ref "R29") (pin "2") (pinfunction "2_2") (pintype "passive"))
    )
    (net (code "33") (name "Net-(D1-A)") (class "Default")
      (node (ref "D1") (pin "1") (pinfunction "A_1") (pintype "passive"))
      (node (ref "D2") (pin "2") (pinfunction "C_2") (pintype "passive"))
      (node (ref "R14") (pin "1") (pinfunction "1_1") (pintype "passive"))
      (node (ref "S1") (pin "3") (pinfunction "S_3") (pintype "passive"))
    )
    (net (code "34") (name "Net-(D1-AC)") (class "Default")
      (node (ref "D1") (pin "3") (pinfunction "AC_3") (pintype "passive"))
      (node (ref "R14") (pin "2") (pinfunction "2_2") (pintype "passive"))
    )
    (net (code "35") (name "Net-(D1-C)") (class "Default")
      (node (ref "D1") (pin "2") (pinfunction "C_2") (pintype "passive"))
      (node (ref "R16") (pin "1") (pinfunction "1_1") (pintype "passive"))
    )
    (net (code "36") (name "Net-(D2-A)") (class "Default")
      (node (ref "C11") (pin "2") (pinfunction "2_2") (pintype "passive"))
      (node (ref "C12") (pin "1") (pinfunction "1_1") (pintype "passive"))
      (node (ref "C20") (pin "1") (pinfunction "1_1") (pintype "passive"))
      (node (ref "D2") (pin "1") (pinfunction "A_1") (pintype "passive"))
      (node (ref "GAIN") (pin "P$2") (pinfunction "S_P$2") (pintype "passive"))
      (node (ref "GAIN") (pin "P$3") (pinfunction "E_P$3") (pintype "passive"))
      (node (ref "R16") (pin "2") (pinfunction "2_2") (pintype "passive"))
      (node (ref "U1") (pin "1") (pinfunction "OUT_1") (pintype "output"))
    )
    (net (code "37") (name "Net-(FB1-Pad1)") (class "Default")
      (node (ref "FB1") (pin "1") (pinfunction "1_1") (pintype "passive"))
      (node (ref "J1") (pin "T") (pinfunction "T_T") (pintype "passive"))
    )
    (net (code "38") (name "Net-(GAIN-A)") (class "Default")
      (node (ref "GAIN") (pin "P$1") (pinfunction "A_P$1") (pintype "passive"))
      (node (ref "R19") (pin "2") (pinfunction "2_2") (pintype "passive"))
    )
    (net (code "39") (name "Net-(LED1-PadA)") (class "Default")
      (node (ref "LED1") (pin "A") (pinfunction "A_A") (pintype "passive"))
      (node (ref "R37") (pin "2") (pinfunction "2_2") (pintype "passive"))
    )
    (net (code "40") (name "Net-(MIX-A)") (class "Default")
      (node (ref "C20") (pin "2") (pinfunction "2_2") (pintype "passive"))
      (node (ref "MIX") (pin "P$1") (pinfunction "A_P$1") (pintype "passive"))
    )
    (net (code "41") (name "Net-(MIX-E)") (class "Default")
      (node (ref "C2") (pin "2") (pinfunction "2_2") (pintype "passive"))
      (node (ref "MIX") (pin "P$3") (pinfunction "E_P$3") (pintype "passive"))
    )
    (net (code "42") (name "Net-(R4-Pad1)") (class "Default")
      (node (ref "R4") (pin "1") (pinfunction "1_1") (pintype "passive"))
      (node (ref "R5") (pin "2") (pinfunction "2_2") (pintype "passive"))
      (node (ref "T1") (pin "B") (pinfunction "B_B") (pintype "passive"))
    )
    (net (code "43") (name "Net-(R29-Pad1)") (class "Default")
      (node (ref "R29") (pin "1") (pinfunction "1_1") (pintype "passive"))
      (node (ref "R32") (pin "2") (pinfunction "2_2") (pintype "passive"))
      (node (ref "T3") (pin "E") (pinfunction "E_E") (pintype "passive"))
    )
    (net (code "44") (name "Net-(RV1-E)") (class "Default")
      (node (ref "R35") (pin "1") (pinfunction "1_1") (pintype "passive"))
      (node (ref "RV1") (pin "1") (pinfunction "E_1") (pintype "passive"))
    )
    (net (code "45") (name "Net-(S1-P)") (class "Default")
      (node (ref "C11") (pin "1") (pinfunction "1_1") (pintype "passive"))
      (node (ref "C8") (pin "2") (pinfunction "2_2") (pintype "passive"))
      (node (ref "C9") (pin "2") (pinfunction "2_2") (pintype "passive"))
      (node (ref "R19") (pin "1") (pinfunction "1_1") (pintype "passive"))
      (node (ref "S1") (pin "2") (pinfunction "P_2") (pintype "passive"))
      (node (ref "U1") (pin "2") (pinfunction "-IN_2") (pintype "input"))
    )
    (net (code "46") (name "Net-(TONE-A)") (class "Default")
      (node (ref "C27") (pin "2") (pinfunction "2_2") (pintype "passive"))
      (node (ref "R22") (pin "1") (pinfunction "1_1") (pintype "passive"))
      (node (ref "R23") (pin "2") (pinfunction "2_2") (pintype "passive"))
      (node (ref "TONE") (pin "P$1") (pinfunction "A_P$1") (pintype "passive"))
      (node (ref "U3") (pin "3") (pinfunction "+IN_3") (pintype "input"))
    )
    (net (code "47") (name "Net-(TONE-E)") (class "Default")
      (node (ref "R27") (pin "1") (pinfunction "1_1") (pintype "passive"))
      (node (ref "TONE") (pin "P$3") (pinfunction "E_P$3") (pintype "passive"))
    )
    (net (code "48") (name "Net-(TONE-S)") (class "Default")
      (node (ref "C28") (pin "2") (pinfunction "2_2") (pintype "passive"))
      (node (ref "TONE") (pin "P$2") (pinfunction "S_P$2") (pintype "passive"))
    )
    (net (code "49") (name "Net-(U1A-+IN)") (class "Default")
      (node (ref "R6") (pin "1") (pinfunction "1_1") (pintype "passive"))
      (node (ref "R9") (pin "2") (pinfunction "2_2") (pintype "passive"))
      (node (ref "U1") (pin "3") (pinfunction "+IN_3") (pintype "input"))
    )
    (net (code "50") (name "Net-(U1B-+IN)") (class "Default")
      (node (ref "C1") (pin "2") (pinfunction "2_2") (pintype "passive"))
      (node (ref "R3") (pin "2") (pinfunction "2_2") (pintype "passive"))
      (node (ref "U1") (pin "5") (pinfunction "+IN_5") (pintype "input"))
    )
    (net (code "51") (name "Net-(U1B--IN)") (class "Default")
      (node (ref "C2") (pin "1") (pinfunction "1_1") (pintype "passive"))
      (node (ref "U1") (pin "6") (pinfunction "-IN_6") (pintype "input"))
      (node (ref "U1") (pin "7") (pinfunction "OUT_7") (pintype "output"))
    )
    (net (code "52") (name "Net-(U3A--IN)") (class "Default")
      (node (ref "C29") (pin "1") (pinfunction "1_1") (pintype "passive"))
      (node (ref "R27") (pin "2") (pinfunction "2_2") (pintype "passive"))
      (node (ref "R33") (pin "1") (pinfunction "1_1") (pintype "passive"))
      (node (ref "U3") (pin "2") (pinfunction "-IN_2") (pintype "input"))
    )
    (net (code "53") (name "Net-(U3A-OUT)") (class "Default")
      (node (ref "C25") (pin "1") (pinfunction "1_1") (pintype "passive"))
      (node (ref "C29") (pin "2") (pinfunction "2_2") (pintype "passive"))
      (node (ref "R33") (pin "2") (pinfunction "2_2") (pintype "passive"))
      (node (ref "U3") (pin "1") (pinfunction "OUT_1") (pintype "output"))
    )
    (net (code "54") (name "Net-(U3B--IN)") (class "Default")
      (node (ref "C24") (pin "1") (pinfunction "1_1") (pintype "passive"))
      (node (ref "U3") (pin "6") (pinfunction "-IN_6") (pintype "input"))
      (node (ref "U3") (pin "7") (pinfunction "OUT_7") (pintype "output"))
    )
    (net (code "55") (name "Net-(U4-FB)") (class "Default")
      (node (ref "R34") (pin "1") (pinfunction "1_1") (pintype "passive"))
      (node (ref "R36") (pin "2") (pinfunction "2_2") (pintype "passive"))
      (node (ref "U4") (pin "1") (pinfunction "FB_1") (pintype "passive"))
    )
    (net (code "56") (name "Net-(U5-FB)") (class "Default")
      (node (ref "R39") (pin "1") (pinfunction "1_1") (pintype "passive"))
      (node (ref "R41") (pin "2") (pinfunction "2_2") (pintype "passive"))
      (node (ref "TP4") (pin "TP") (pinfunction "TP_TP") (pintype "input"))
      (node (ref "U5") (pin "5") (pinfunction "FB_5") (pintype "passive"))
    )
    (net (code "57") (name "Net-(U5-PG)") (class "Default")
      (node (ref "R40") (pin "1") (pinfunction "1_1") (pintype "passive"))
      (node (ref "TP5") (pin "TP") (pinfunction "TP_TP") (pintype "input"))
      (node (ref "U5") (pin "7") (pinfunction "PG_7") (pintype "passive"))
    )
    (net (code "58") (name "Net-(U5-SW)") (class "Default")
      (node (ref "L1") (pin "1") (pinfunction "1_1") (pintype "passive"))
      (node (ref "U5") (pin "9") (pinfunction "SW_9") (pintype "passive"))
    )
    (net (code "59") (name "Net-(VOL-E)") (class "Default")
      (node (ref "R25") (pin "2") (pinfunction "2_2") (pintype "passive"))
      (node (ref "VOL") (pin "P$3") (pinfunction "E_P$3") (pintype "passive"))
    )
    (net (code "60") (name "Net-(VOL-S)") (class "Default")
      (node (ref "C26") (pin "1") (pinfunction "1_1") (pintype "passive"))
      (node (ref "VOL") (pin "P$2") (pinfunction "S_P$2") (pintype "passive"))
    )
    (net (code "61") (name "Net-(VR1-E)") (class "Default")
      (node (ref "R1") (pin "1") (pinfunction "1_1") (pintype "passive"))
      (node (ref "VR1") (pin "1") (pinfunction "E_1") (pintype "passive"))
      (node (ref "VR1") (pin "2") (pinfunction "S_2") (pintype "passive"))
    )
    (net (code "62") (name "Net-(VR2-E)") (class "Default")
      (node (ref "R2") (pin "1") (pinfunction "1_1") (pintype "passive"))
      (node (ref "VR2") (pin "1") (pinfunction "E_1") (pintype "passive"))
      (node (ref "VR2") (pin "2") (pinfunction "S_2") (pintype "passive"))
    )
    (net (code "63") (name "OUT") (class "Default")
      (node (ref "FB2") (pin "2") (pinfunction "2_2") (pintype "passive"))
      (node (ref "J3") (pin "T") (pinfunction "T_T") (pintype "passive"))
    )
    (net (code "64") (name "unconnected-(D2-AC-Pad3)") (class "Default")
      (node (ref "D2") (pin "3") (pinfunction "AC_3") (pintype "passive"))
    )
    (net (code "65") (name "unconnected-(S1-G1-Pad4)") (class "Default")
      (node (ref "S1") (pin "4") (pinfunction "G1_4") (pintype "bidirectional"))
    )
    (net (code "66") (name "unconnected-(S1-G2-Pad5)") (class "Default")
      (node (ref "S1") (pin "5") (pinfunction "G2_5") (pintype "bidirectional"))
    )
    (net (code "67") (name "unconnected-(S1-O-Pad1)") (class "Default")
      (node (ref "S1") (pin "1") (pinfunction "O_1") (pintype "passive"))
    )
    (net (code "68") (name "unconnected-(U5-NC-Pad4)") (class "Default")
      (node (ref "U5") (pin "4") (pinfunction "NC_4") (pintype "passive"))
    )
  )
)
